# Sheet_V1_0.net
KiCad netlist of a schematic drawn in Altium Designer
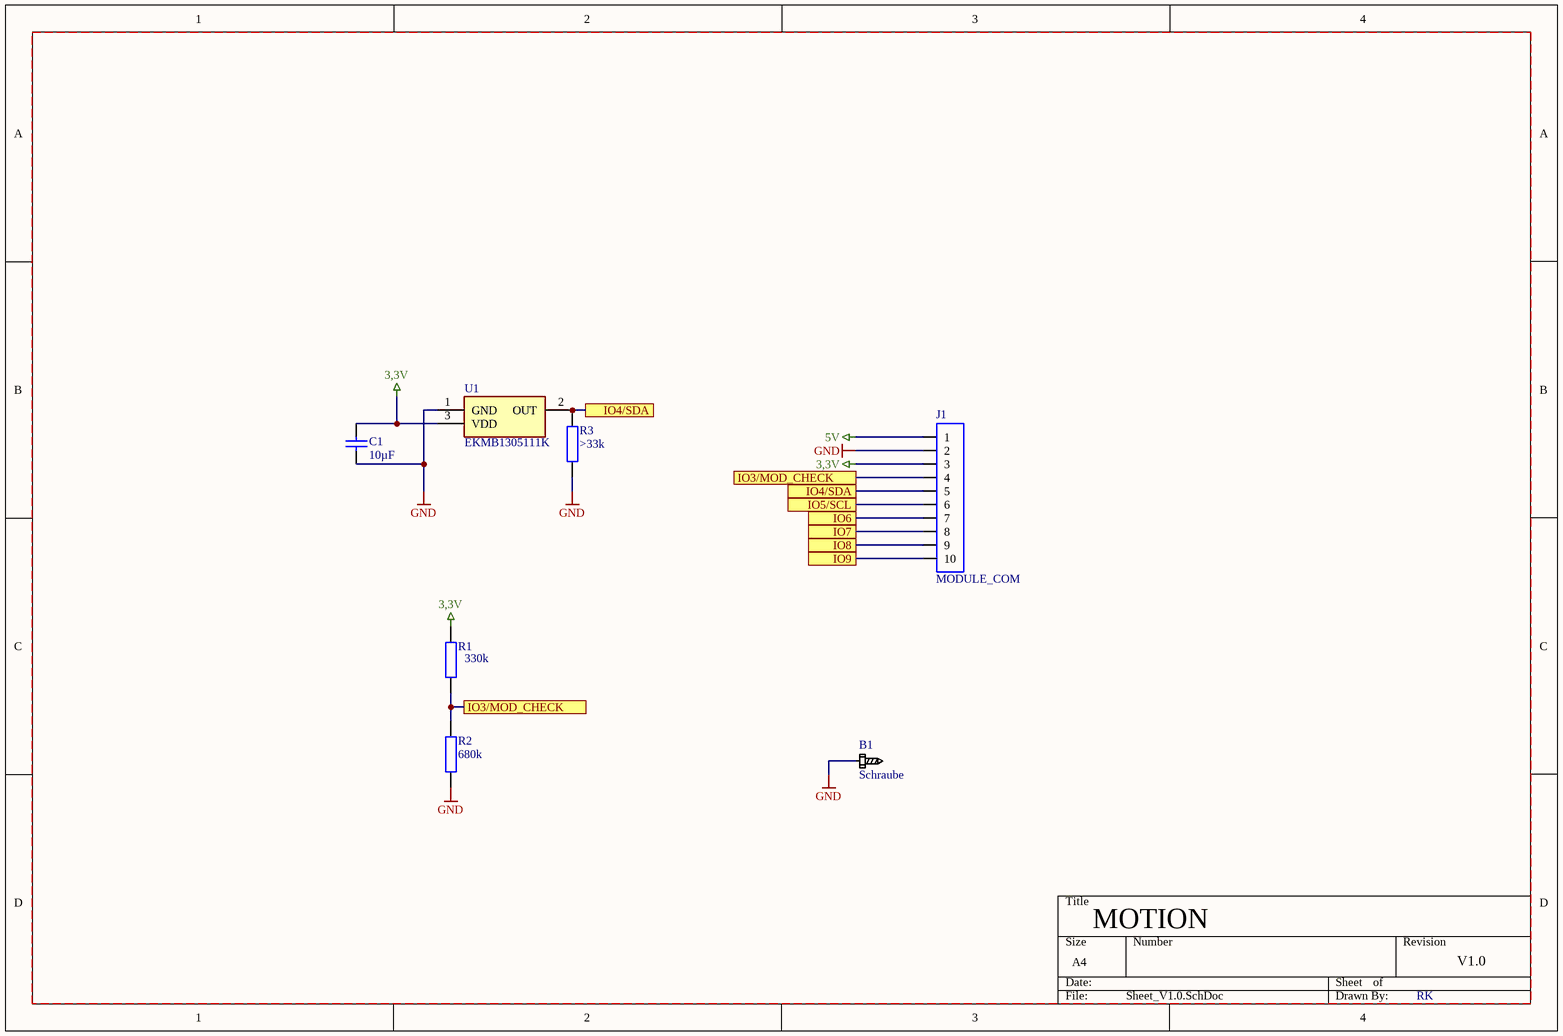
[diagram p0: Sheet_V1.0.SchDoc]

(export (version "E")
  (design (tool "Eeschema 10.0.6"))
  (components
    (comp (ref "B1")
      (value "Schraube")
      (footprint "B_Schraube-M3 PAD")
      (description "Schraubenloch für M3 Schrauben")
      (libsource (lib "SCHLIB-PCSB_5.1.3") (part "B_Schraube"))
    )
    (comp (ref "C1")
      (value "10µF")
      (footprint "C_SMD_0603")
      (description "Kondensator SMD Universal, Keramik, Folie, usw.")
      (libsource (lib "SCHLIB-PCSB_5.1.3") (part "C_SMD_KO"))
    )
    (comp (ref "J1")
      (value "MODULE_COM")
      (footprint "SIP-10")
      (description "Stecker")
      (libsource (lib "SCHLIB-PCSB_5.1.3") (part "J_THT_CON10"))
    )
    (comp (ref "R1")
      (value "330k")
      (footprint "R_SMD_0805")
      (description "Widerstand SMD")
      (libsource (lib "SCHLIB-PCSB_5.1.3") (part "R_SMD_Widerstand"))
    )
    (comp (ref "R2")
      (value "680k")
      (footprint "R_SMD_0805")
      (description "Widerstand SMD")
      (libsource (lib "SCHLIB-PCSB_5.1.3") (part "R_SMD_Widerstand"))
    )
    (comp (ref "R3")
      (value ">33k")
      (footprint "R_SMD_0805")
      (description "Widerstand SMD")
      (libsource (lib "SCHLIB-PCSB_5.1.3") (part "R_SMD_Widerstand"))
    )
    (comp (ref "U1")
      (value "EKMB1305111K")
      (footprint "SamacSys:EKMB1305111K")
      (description "Undefined or Miscellaneous")
      (fields (field (name "MOUSER PART NUMBER") "667-EKMB1305111K"))
      (libsource (lib "*") (part "EKMB1305111K"))
    )
  )
  (nets
    (net (code "1") (name "/IO3{slash}MOD_CHECK") (class "Default")
      (node (ref "J1") (pin "4") (pinfunction "4_4") (pintype "passive"))
      (node (ref "R1") (pin "1") (pintype "passive"))
      (node (ref "R2") (pin "2") (pintype "passive"))
    )
    (net (code "2") (name "/IO4{slash}SDA") (class "Default")
      (node (ref "J1") (pin "5") (pinfunction "5_5") (pintype "passive"))
      (node (ref "R3") (pin "2") (pintype "passive"))
      (node (ref "U1") (pin "2") (pinfunction "OUT_2") (pintype "passive"))
    )
    (net (code "3") (name "/IO5{slash}SCL") (class "Default")
      (node (ref "J1") (pin "6") (pinfunction "6_6") (pintype "passive"))
    )
    (net (code "4") (name "/IO6") (class "Default")
      (node (ref "J1") (pin "7") (pinfunction "7_7") (pintype "passive"))
    )
    (net (code "5") (name "/IO7") (class "Default")
      (node (ref "J1") (pin "8") (pinfunction "8_8") (pintype "passive"))
    )
    (net (code "6") (name "/IO8") (class "Default")
      (node (ref "J1") (pin "9") (pinfunction "9_9") (pintype "passive"))
    )
    (net (code "7") (name "/IO9") (class "Default")
      (node (ref "J1") (pin "10") (pinfunction "10_10") (pintype "passive"))
    )
    (net (code "8") (name "3,3V") (class "Default")
      (node (ref "C1") (pin "2") (pintype "passive"))
      (node (ref "J1") (pin "3") (pinfunction "3_3") (pintype "passive"))
      (node (ref "R1") (pin "2") (pintype "passive"))
      (node (ref "U1") (pin "3") (pinfunction "VDD_3") (pintype "passive"))
    )
    (net (code "9") (name "5V") (class "Default")
      (node (ref "J1") (pin "1") (pinfunction "1_1") (pintype "passive"))
    )
    (net (code "10") (name "GND") (class "Default")
      (node (ref "B1") (pin "1") (pinfunction "PAD_1") (pintype "passive"))
      (node (ref "C1") (pin "1") (pintype "passive"))
      (node (ref "J1") (pin "2") (pinfunction "2_2") (pintype "passive"))
      (node (ref "R2") (pin "1") (pintype "passive"))
      (node (ref "R3") (pin "1") (pintype "passive"))
      (node (ref "U1") (pin "1") (pinfunction "GND_1") (pintype "passive"))
    )
  )
)
